# current_clamp_module.net
KiCad netlist of a schematic drawn in EAGLE
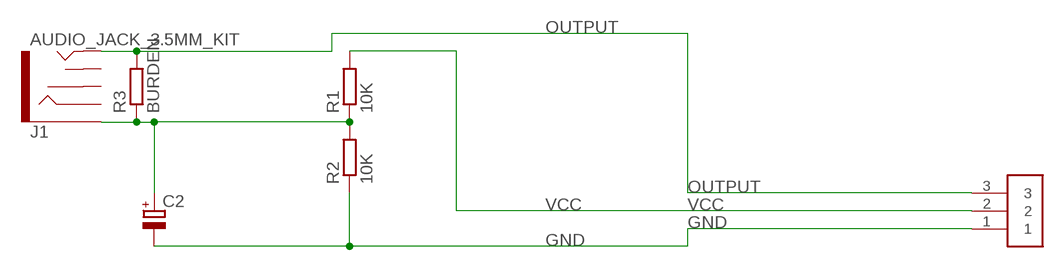
[diagram p0: schematic, sheet 1]
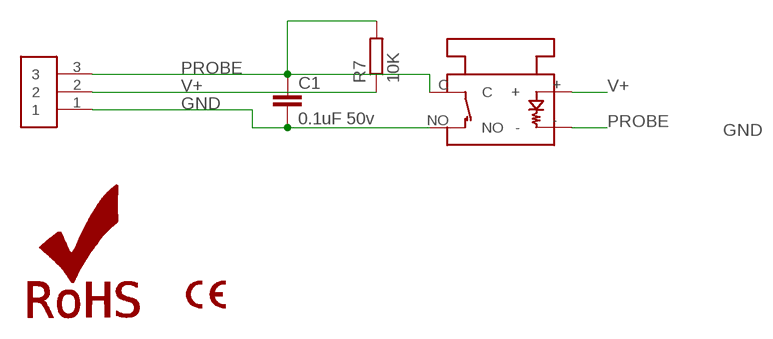
[diagram p1: schematic, sheet 2]

(export (version "E")
  (design (tool "Eeschema 10.0.6"))
  (components
    (comp (ref "C1")
      (value "0.1uF 50v")
      (footprint "eagle-import:C1206")
      (libsource (lib "eagle-import") (part "C-EUC1206"))
    )
    (comp (ref "LOGO1")
      (value "ROHS_LOGO")
      (footprint "eagle-import:ROHS_LOGO_0.18_IN")
      (libsource (lib "eagle-import") (part "ROHS_LOGO"))
    )
    (comp (ref "LOGO2")
      (value "CE-4MM")
      (footprint "eagle-import:CE-4MM")
      (libsource (lib "eagle-import") (part "CE-4MM"))
    )
    (comp (ref "PROBE")
      (value "Phoenix Pluggable 3.81mm 3 way")
      (footprint "eagle-import:3.81MM-3WAY-PLUGGABLE-SCREW")
      (libsource (lib "eagle-import") (part "CONNECTOR-M3"))
    )
    (comp (ref "R7")
      (value "10K")
      (footprint "eagle-import:M1206")
      (libsource (lib "eagle-import") (part "R-EU_M1206"))
    )
    (comp (ref "U$1")
      (value "25MMVANDALSWITCH")
      (footprint "eagle-import:25MMVANDALSWITCH")
      (libsource (lib "eagle-import") (part "25MMVANDALSWITCH"))
    )
    (comp (ref "ACCURR\\")
      (value "Phoenix Pluggable 3.81mm 3 way")
      (footprint "eagle-import:3.81MM-3WAY-PLUGGABLE-SCREW")
      (libsource (lib "eagle-import") (part "CONNECTOR-M3"))
    )
    (comp (ref "C2")
      (value "CPOL-EUE2.5-6")
      (footprint "eagle-import:E2,5-6")
      (libsource (lib "eagle-import") (part "CPOL-EUE2.5-6"))
    )
    (comp (ref "J1")
      (value "AUDIO_JACK_3.5MM_KIT")
      (footprint "eagle-import:AUDIO-JACK-KIT")
      (libsource (lib "eagle-import") (part "AUDIO_JACK_3.5MM_KIT"))
    )
    (comp (ref "R1")
      (value "10K")
      (footprint "eagle-import:M1206")
      (libsource (lib "eagle-import") (part "R-EU_M1206"))
    )
    (comp (ref "R2")
      (value "10K")
      (footprint "eagle-import:M1206")
      (libsource (lib "eagle-import") (part "R-EU_M1206"))
    )
    (comp (ref "R3")
      (value "BURDEN")
      (footprint "eagle-import:M1206")
      (libsource (lib "eagle-import") (part "R-EU_M1206"))
    )
  )
  (nets
    (net (code "1") (name "GND") (class "Default")
      (node (ref "ACCURR\\") (pin "1") (pinfunction "1_1") (pintype "bidirectional"))
      (node (ref "C1") (pin "2") (pinfunction "2_2") (pintype "passive"))
      (node (ref "C2") (pin "-") (pinfunction "-_-") (pintype "passive"))
      (node (ref "PROBE") (pin "1") (pinfunction "1_1") (pintype "bidirectional"))
      (node (ref "R2") (pin "1") (pinfunction "1_1") (pintype "passive"))
      (node (ref "U$1") (pin "NO") (pinfunction "NO_NO") (pintype "bidirectional"))
    )
    (net (code "2") (name "Net-(C2-Pad+)") (class "Default")
      (node (ref "C2") (pin "+") (pinfunction "+_+") (pintype "passive"))
      (node (ref "J1") (pin "SLEEVE") (pinfunction "SLEEVE_SLEEVE") (pintype "bidirectional"))
      (node (ref "R1") (pin "1") (pinfunction "1_1") (pintype "passive"))
      (node (ref "R2") (pin "2") (pinfunction "2_2") (pintype "passive"))
      (node (ref "R3") (pin "1") (pinfunction "1_1") (pintype "passive"))
    )
    (net (code "3") (name "OUTPUT") (class "Default")
      (node (ref "ACCURR\\") (pin "3") (pinfunction "3_3") (pintype "bidirectional"))
      (node (ref "J1") (pin "TIP") (pinfunction "TIP_TIP") (pintype "bidirectional"))
      (node (ref "R3") (pin "2") (pinfunction "2_2") (pintype "passive"))
    )
    (net (code "4") (name "PROBE") (class "Default")
      (node (ref "C1") (pin "1") (pinfunction "1_1") (pintype "passive"))
      (node (ref "PROBE") (pin "3") (pinfunction "3_3") (pintype "bidirectional"))
      (node (ref "R7") (pin "2") (pinfunction "2_2") (pintype "passive"))
      (node (ref "U$1") (pin "-") (pinfunction "-_-") (pintype "bidirectional"))
      (node (ref "U$1") (pin "C") (pinfunction "C_C") (pintype "bidirectional"))
    )
    (net (code "5") (name "V+") (class "Default")
      (node (ref "PROBE") (pin "2") (pinfunction "2_2") (pintype "bidirectional"))
      (node (ref "R7") (pin "1") (pinfunction "1_1") (pintype "passive"))
      (node (ref "U$1") (pin "+") (pinfunction "+_+") (pintype "bidirectional"))
    )
    (net (code "6") (name "VCC") (class "Default")
      (node (ref "ACCURR\\") (pin "2") (pinfunction "2_2") (pintype "bidirectional"))
      (node (ref "R1") (pin "2") (pinfunction "2_2") (pintype "passive"))
    )
    (net (code "7") (name "unconnected-(J1-PadRING)") (class "Default")
      (node (ref "J1") (pin "RING") (pinfunction "RING_RING") (pintype "bidirectional"))
    )
    (net (code "8") (name "unconnected-(J1-PadRSH)") (class "Default")
      (node (ref "J1") (pin "RSH") (pinfunction "RSH_RSH") (pintype "bidirectional"))
    )
    (net (code "9") (name "unconnected-(J1-PadTSH)") (class "Default")
      (node (ref "J1") (pin "TSH") (pinfunction "TSH_TSH") (pintype "bidirectional"))
    )
  )
)
